# ZX1541_Interfac_in_THT.net
KiCad netlist of a schematic drawn in Altium Designer
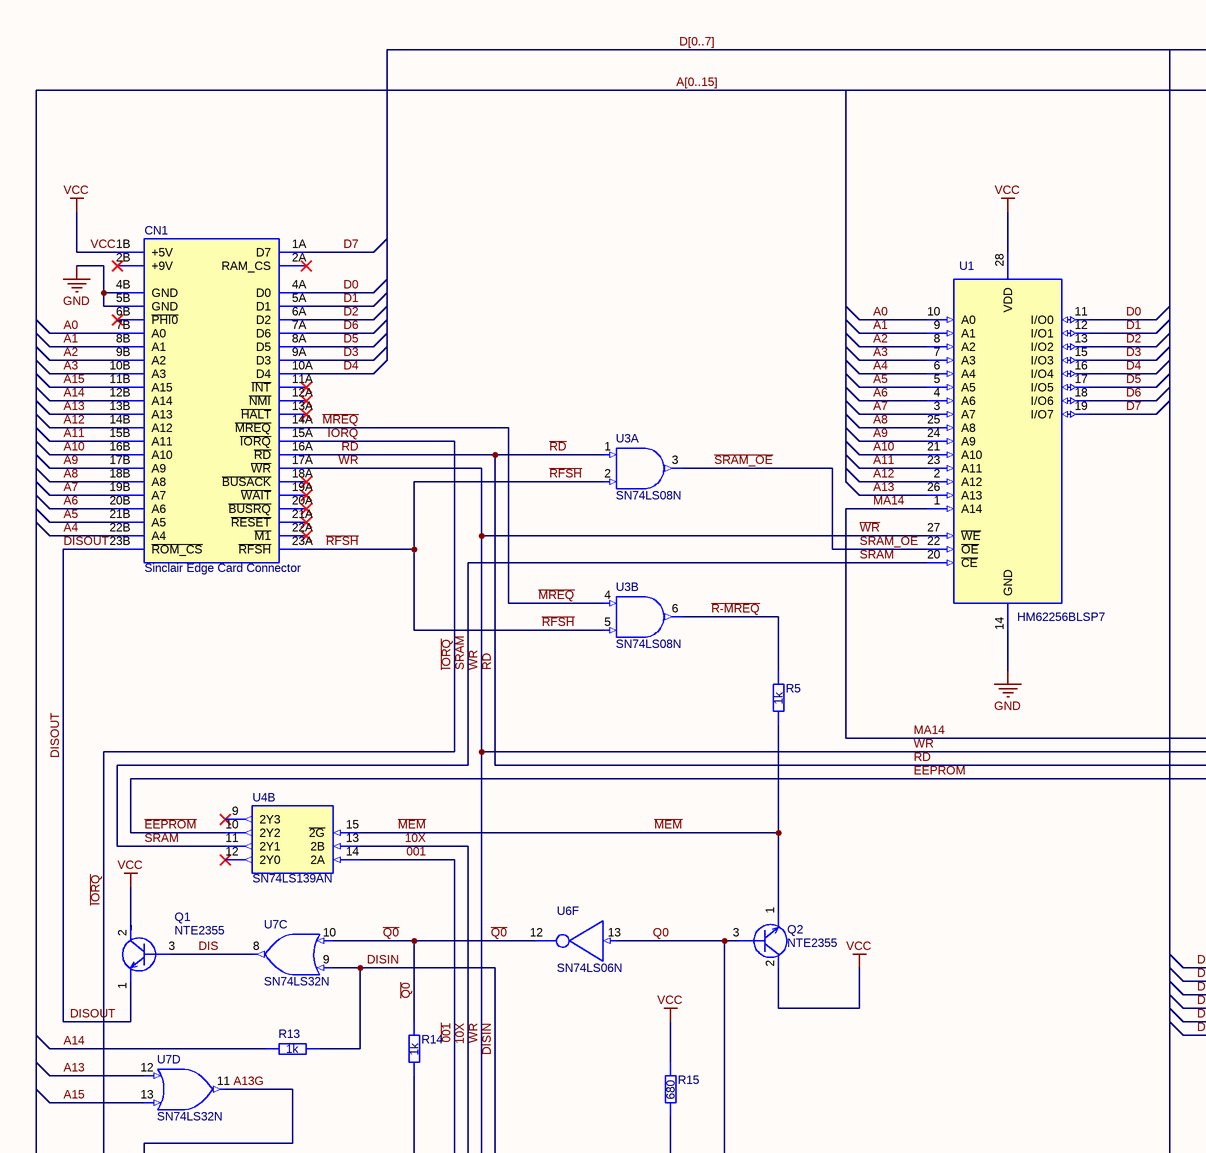
[diagram p0: ZX1541 Interfac in THT.SchDoc, top left]
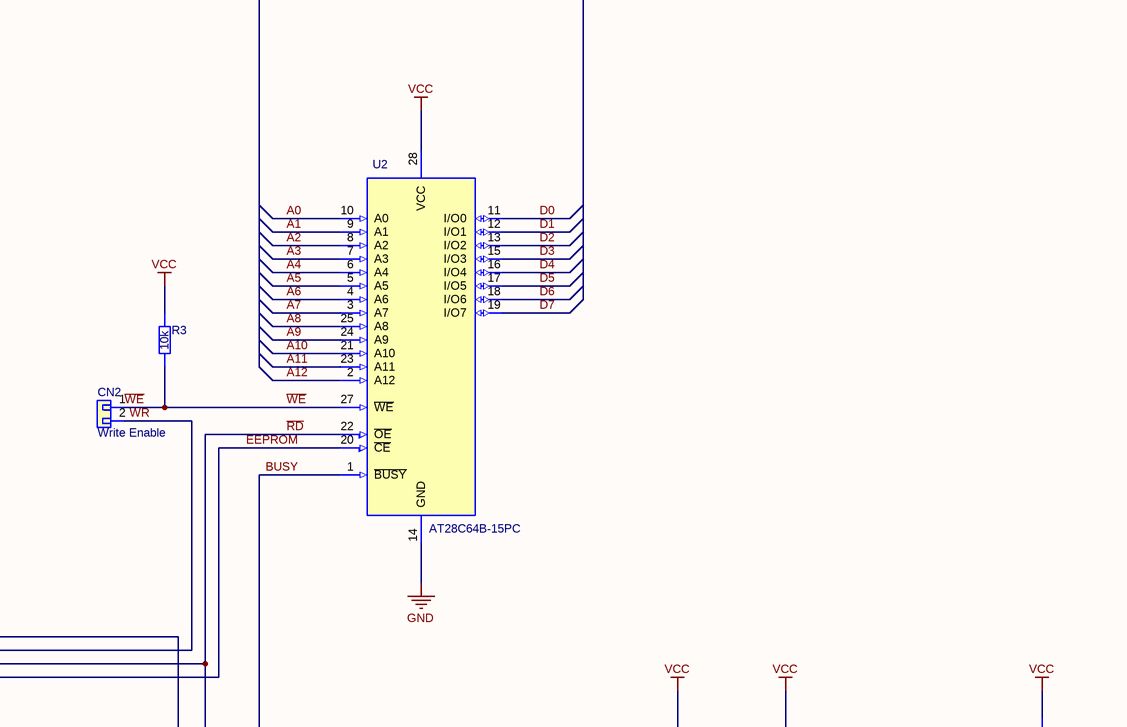
[diagram p1: ZX1541 Interfac in THT.SchDoc, top right]
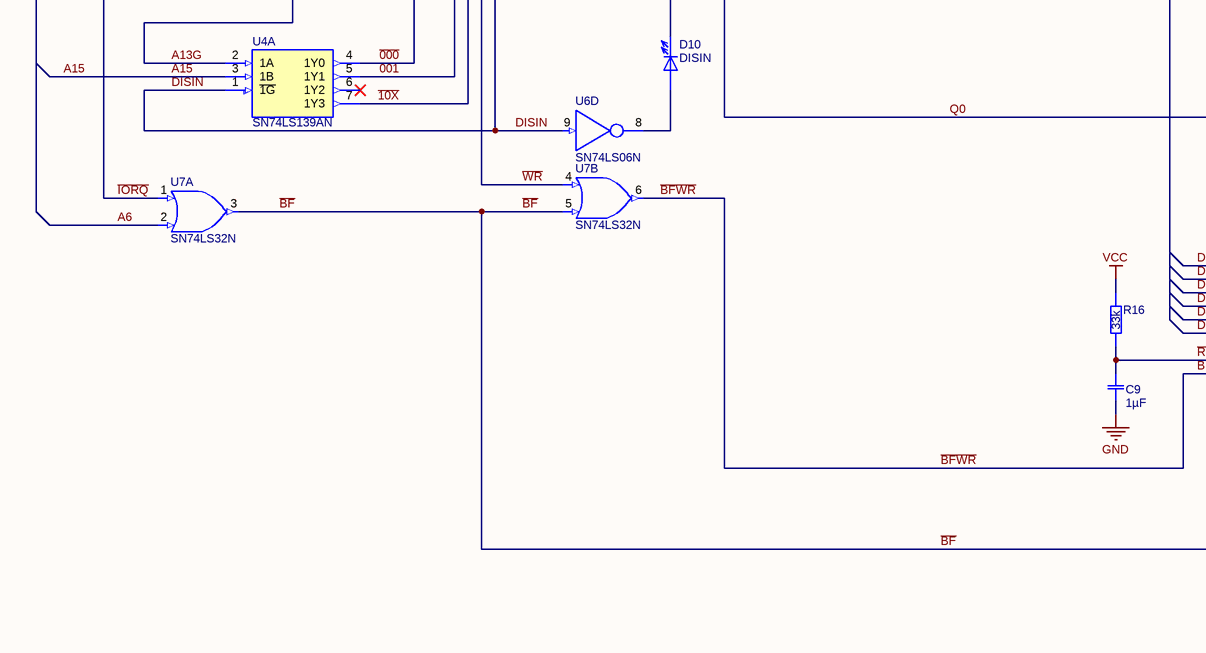
[diagram p2: ZX1541 Interfac in THT.SchDoc, bottom left]
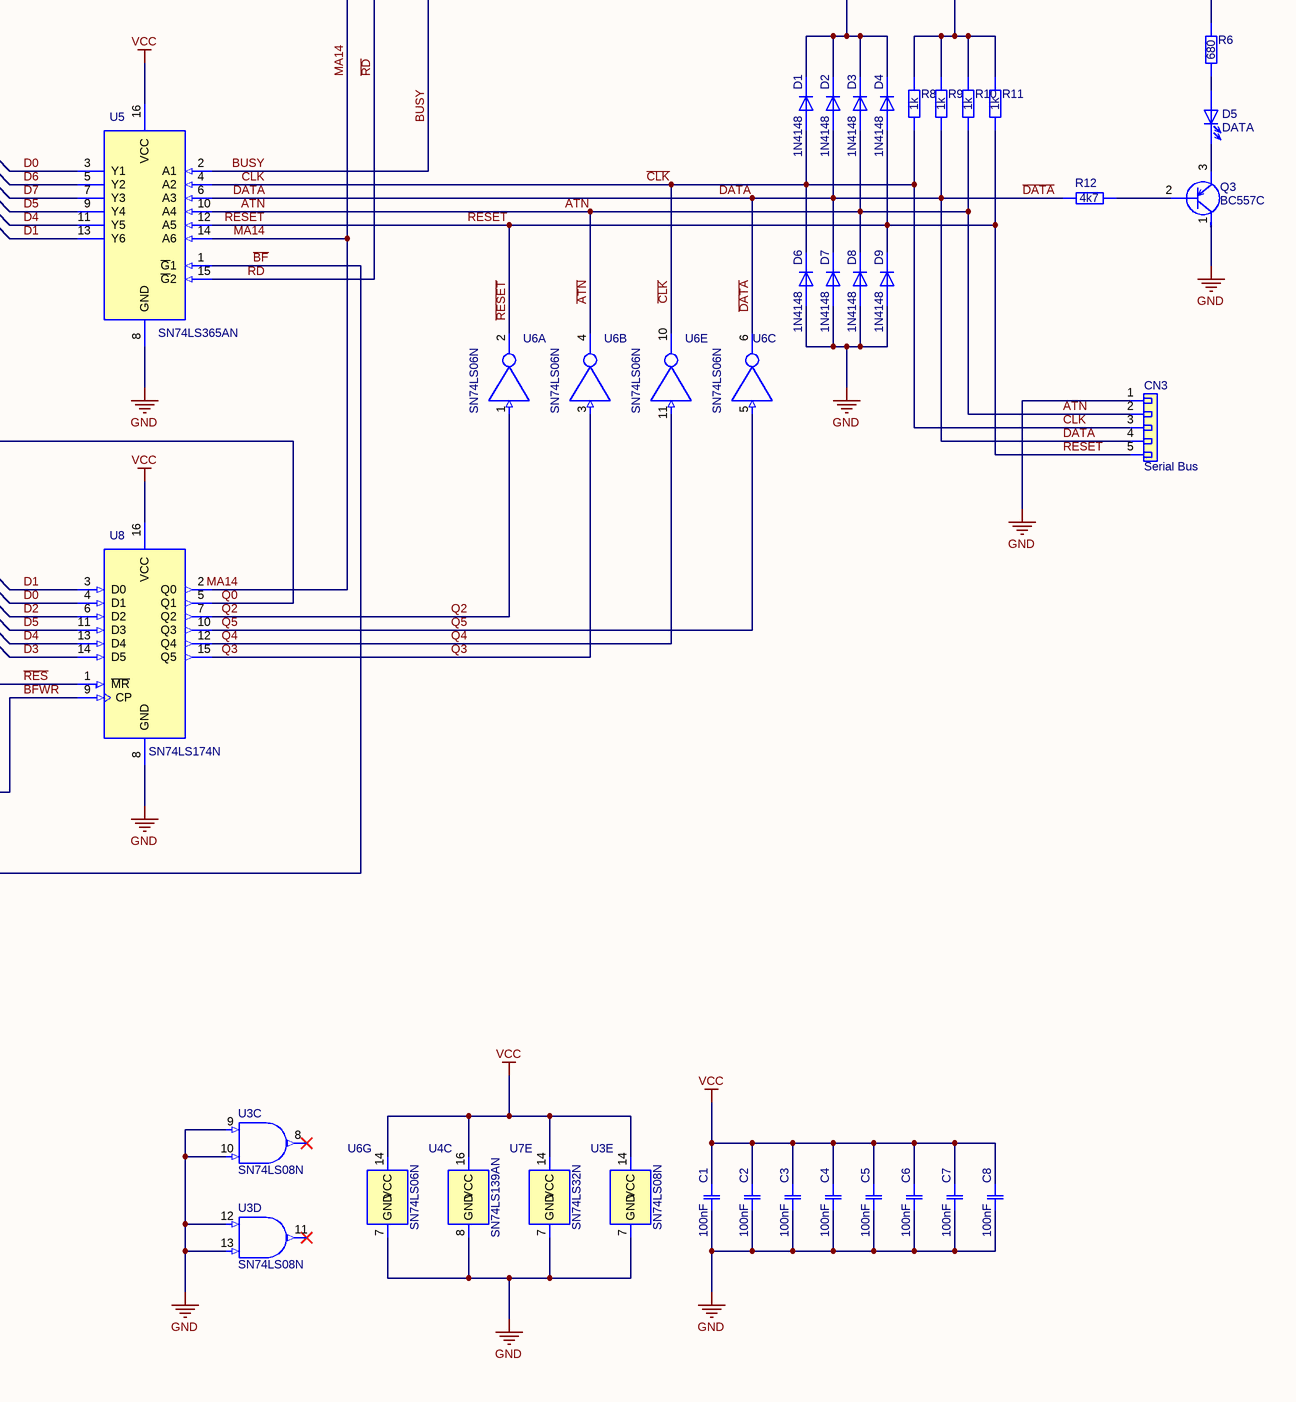
[diagram p3: ZX1541 Interfac in THT.SchDoc, bottom right]

(export (version "E")
  (design (tool "Eeschema 10.0.6"))
  (components
    (comp (ref "C1")
      (value "100nF")
      (footprint "CAP Disc 100nF P2.54mm D5.5mm T3mm")
      (description "Ceramic Disc Capacitors 100nF -20%~+80% 50V Through Hole,P=2.54mm RoHS")
      (libsource (lib "PCB-Tech Cloud") (part "Capacitor"))
    )
    (comp (ref "C2")
      (value "100nF")
      (footprint "CAP Disc 100nF P2.54mm D5.5mm T3mm")
      (description "Ceramic Disc Capacitors 100nF -20%~+80% 50V Through Hole,P=2.54mm RoHS")
      (libsource (lib "PCB-Tech Cloud") (part "Capacitor"))
    )
    (comp (ref "C3")
      (value "100nF")
      (footprint "CAP Disc 100nF P2.54mm D5.5mm T3mm")
      (description "Ceramic Disc Capacitors 100nF -20%~+80% 50V Through Hole,P=2.54mm RoHS")
      (libsource (lib "PCB-Tech Cloud") (part "Capacitor"))
    )
    (comp (ref "C4")
      (value "100nF")
      (footprint "CAP Disc 100nF P2.54mm D5.5mm T3mm")
      (description "Ceramic Disc Capacitors 100nF -20%~+80% 50V Through Hole,P=2.54mm RoHS")
      (libsource (lib "PCB-Tech Cloud") (part "Capacitor"))
    )
    (comp (ref "C5")
      (value "100nF")
      (footprint "CAP Disc 100nF P2.54mm D5.5mm T3mm")
      (description "Ceramic Disc Capacitors 100nF -20%~+80% 50V Through Hole,P=2.54mm RoHS")
      (libsource (lib "PCB-Tech Cloud") (part "Capacitor"))
    )
    (comp (ref "C6")
      (value "100nF")
      (footprint "CAP Disc 100nF P2.54mm D5.5mm T3mm")
      (description "Ceramic Disc Capacitors 100nF -20%~+80% 50V Through Hole,P=2.54mm RoHS")
      (libsource (lib "PCB-Tech Cloud") (part "Capacitor"))
    )
    (comp (ref "C7")
      (value "100nF")
      (footprint "CAP Disc 100nF P2.54mm D5.5mm T3mm")
      (description "Ceramic Disc Capacitors 100nF -20%~+80% 50V Through Hole,P=2.54mm RoHS")
      (libsource (lib "PCB-Tech Cloud") (part "Capacitor"))
    )
    (comp (ref "C8")
      (value "100nF")
      (footprint "CAP Disc 100nF P2.54mm D5.5mm T3mm")
      (description "Ceramic Disc Capacitors 100nF -20%~+80% 50V Through Hole,P=2.54mm RoHS")
      (libsource (lib "PCB-Tech Cloud") (part "Capacitor"))
    )
    (comp (ref "C9")
      (value "1µF")
      (footprint "CAP 1µF C315C105K3R5TA P2.54mm")
      (description "Multilayer Ceramic Capacitors MLCC - Leaded 25volts 1uF 10% X7R")
      (fields (field (name "VOLTAGE") "25V") (field (name "TOLERANCE") "10%"))
      (libsource (lib "PCB-Tech Cloud") (part "Capacitor"))
    )
    (comp (ref "CN1")
      (value "Sinclair Edge Card Connector")
      (footprint "Sinclair Card Connector")
      (libsource (lib "PCB-Tech Cloud") (part "Sinclair Expansion Port Connector"))
    )
    (comp (ref "CN2")
      (value "Write Enable")
      (footprint "Pin Header 01x02 2.54mm Horizontal Male")
      (description "CONN HEADER .100\" SNGL STR 2POS")
      (libsource (lib "PCB-Tech Cloud") (part "CONN 01x02"))
    )
    (comp (ref "CN3")
      (value "Serial Bus")
      (footprint "01x05 RM2.0 mm Male Pin Header - MPE-Garry 150-1-005-0-S-XS0-0835")
      (description "Conn Unshrouded Header HDR 5 POS 2mm Solder ST Thru-Hole Automotive Bulk")
      (libsource (lib "PCB-Tech Cloud") (part "CONN 01x05"))
    )
    (comp (ref "D1")
      (value "1N4148")
      (footprint "1N4148 P=5.08mm")
      (description "NEXPERIA - 1N4148 - DIODE, 1N4148 AMMO-BOX 10K")
      (fields (field (name "VOLTAGE") "100V"))
      (libsource (lib "PCB-Tech Cloud") (part "Diode Standard"))
    )
    (comp (ref "D2")
      (value "1N4148")
      (footprint "1N4148 P=5.08mm")
      (description "NEXPERIA - 1N4148 - DIODE, 1N4148 AMMO-BOX 10K")
      (fields (field (name "VOLTAGE") "100V"))
      (libsource (lib "PCB-Tech Cloud") (part "Diode Standard"))
    )
    (comp (ref "D3")
      (value "1N4148")
      (footprint "1N4148 P=5.08mm")
      (description "NEXPERIA - 1N4148 - DIODE, 1N4148 AMMO-BOX 10K")
      (fields (field (name "VOLTAGE") "100V"))
      (libsource (lib "PCB-Tech Cloud") (part "Diode Standard"))
    )
    (comp (ref "D4")
      (value "1N4148")
      (footprint "1N4148 P=5.08mm")
      (description "NEXPERIA - 1N4148 - DIODE, 1N4148 AMMO-BOX 10K")
      (fields (field (name "VOLTAGE") "100V"))
      (libsource (lib "PCB-Tech Cloud") (part "Diode Standard"))
    )
    (comp (ref "D5")
      (value "DATA")
      (footprint "LED 3mm Red Right Angle 4mm")
      (description "WURTH ELEKTRONIK   151033RS03000   LED, 3MM,  RED, 2600MCD, 621NM")
      (libsource (lib "PCB-Tech Cloud") (part "LED Standard"))
    )
    (comp (ref "D6")
      (value "1N4148")
      (footprint "1N4148 P=5.08mm")
      (description "NEXPERIA - 1N4148 - DIODE, 1N4148 AMMO-BOX 10K")
      (fields (field (name "VOLTAGE") "100V"))
      (libsource (lib "PCB-Tech Cloud") (part "Diode Standard"))
    )
    (comp (ref "D7")
      (value "1N4148")
      (footprint "1N4148 P=5.08mm")
      (description "NEXPERIA - 1N4148 - DIODE, 1N4148 AMMO-BOX 10K")
      (fields (field (name "VOLTAGE") "100V"))
      (libsource (lib "PCB-Tech Cloud") (part "Diode Standard"))
    )
    (comp (ref "D8")
      (value "1N4148")
      (footprint "1N4148 P=5.08mm")
      (description "NEXPERIA - 1N4148 - DIODE, 1N4148 AMMO-BOX 10K")
      (fields (field (name "VOLTAGE") "100V"))
      (libsource (lib "PCB-Tech Cloud") (part "Diode Standard"))
    )
    (comp (ref "D9")
      (value "1N4148")
      (footprint "1N4148 P=5.08mm")
      (description "NEXPERIA - 1N4148 - DIODE, 1N4148 AMMO-BOX 10K")
      (fields (field (name "VOLTAGE") "100V"))
      (libsource (lib "PCB-Tech Cloud") (part "Diode Standard"))
    )
    (comp (ref "D10")
      (value "DISIN")
      (footprint "LED 3mm Green Right Angle 4mm")
      (libsource (lib "PCB-Tech Cloud") (part "LED Standard"))
    )
    (comp (ref "Q1")
      (value "NTE2355")
      (footprint "NTE 2355")
      (libsource (lib "PCB-Tech Cloud") (part "Transistor NPN ECB"))
    )
    (comp (ref "Q2")
      (value "NTE2355")
      (footprint "NTE 2355")
      (libsource (lib "PCB-Tech Cloud") (part "Transistor NPN ECB"))
    )
    (comp (ref "Q3")
      (value "BC557C")
      (footprint "BC557C")
      (description "Trans GP BJT PNP 45V 0.1A Automotive 3-Pin TO-92 T/R")
      (libsource (lib "PCB-Tech Cloud") (part "Transistor PNP CBE"))
    )
    (comp (ref "R3")
      (value "10k")
      (footprint "10 kOhm R Axial DIN0207 L6.3mm D2.5mm P7.62mm Horizontal")
      (description "RES 10K OHM 1/4W 5% AXIAL")
      (fields (field (name "TOLERANCE") "5%"))
      (libsource (lib "PCB-Tech Cloud") (part "Resistor"))
    )
    (comp (ref "R5")
      (value "1k")
      (footprint "1,0 kOhm R Axial DIN0207 L6.3mm D2.5mm P7.62mm Horizontal")
      (description "RES 1K OHM 1/4W 5% AXIAL")
      (fields (field (name "TOLERANCE") "5%"))
      (libsource (lib "PCB-Tech Cloud") (part "Resistor"))
    )
    (comp (ref "R6")
      (value "680")
      (footprint "680 kOhm R Axial DIN0207 L6.3mm D2.5mm P7.62mm Horizontal")
      (description "Res 680K Ohm 1/4W 5% Axial")
      (fields (field (name "TOLERANCE") "5%"))
      (libsource (lib "PCB-Tech Cloud") (part "Resistor"))
    )
    (comp (ref "R8")
      (value "1k")
      (footprint "1,0 kOhm R Axial DIN0207 L6.3mm D2.5mm P7.62mm Horizontal")
      (description "RES 1K OHM 1/4W 5% AXIAL")
      (fields (field (name "TOLERANCE") "5%"))
      (libsource (lib "PCB-Tech Cloud") (part "Resistor"))
    )
    (comp (ref "R9")
      (value "1k")
      (footprint "1,0 kOhm R Axial DIN0207 L6.3mm D2.5mm P7.62mm Horizontal")
      (description "RES 1K OHM 1/4W 5% AXIAL")
      (fields (field (name "TOLERANCE") "5%"))
      (libsource (lib "PCB-Tech Cloud") (part "Resistor"))
    )
    (comp (ref "R10")
      (value "1k")
      (footprint "1,0 kOhm R Axial DIN0207 L6.3mm D2.5mm P7.62mm Horizontal")
      (description "RES 1K OHM 1/4W 5% AXIAL")
      (fields (field (name "TOLERANCE") "5%"))
      (libsource (lib "PCB-Tech Cloud") (part "Resistor"))
    )
    (comp (ref "R11")
      (value "1k")
      (footprint "1,0 kOhm R Axial DIN0207 L6.3mm D2.5mm P7.62mm Horizontal")
      (description "RES 1K OHM 1/4W 5% AXIAL")
      (fields (field (name "TOLERANCE") "5%"))
      (libsource (lib "PCB-Tech Cloud") (part "Resistor"))
    )
    (comp (ref "R12")
      (value "4k7")
      (footprint "4,7 kOhm R Axial DIN0207 L6.3mm D2.5mm P7.62mm Horizontal")
      (description "RES 4.7K OHM 1/4W 5% AXIAL")
      (fields (field (name "TOLERANCE") "5%"))
      (libsource (lib "PCB-Tech Cloud") (part "Resistor"))
    )
    (comp (ref "R13")
      (value "1k")
      (footprint "1,0 kOhm R Axial DIN0207 L6.3mm D2.5mm P7.62mm Horizontal")
      (description "RES 1K OHM 1/4W 5% AXIAL")
      (fields (field (name "TOLERANCE") "5%"))
      (libsource (lib "PCB-Tech Cloud") (part "Resistor"))
    )
    (comp (ref "R14")
      (value "1k")
      (footprint "1,0 kOhm R Axial DIN0207 L6.3mm D2.5mm P7.62mm Horizontal")
      (description "RES 1K OHM 1/4W 5% AXIAL")
      (fields (field (name "TOLERANCE") "5%"))
      (libsource (lib "PCB-Tech Cloud") (part "Resistor"))
    )
    (comp (ref "R15")
      (value "680")
      (footprint "680 kOhm R Axial DIN0207 L6.3mm D2.5mm P7.62mm Horizontal")
      (description "Res 680K Ohm 1/4W 5% Axial")
      (fields (field (name "TOLERANCE") "5%"))
      (libsource (lib "PCB-Tech Cloud") (part "Resistor"))
    )
    (comp (ref "R16")
      (value "33k")
      (footprint "33 kOhm R Axial DIN0207 L6.3mm D2.5mm P7.62mm Horizontal")
      (description "RES 33K OHM 1/4W 5% AXIAL")
      (fields (field (name "TOLERANCE") "5%"))
      (libsource (lib "PCB-Tech Cloud") (part "Resistor"))
    )
    (comp (ref "U1")
      (value "HM62256BLSP7")
      (footprint "Hitachi HM62256BLSP-7 SRAM 32kx8")
      (description "Contact for details")
      (libsource (lib "PCB-Tech Cloud") (part "HM62256BLSP-7"))
    )
    (comp (ref "U2")
      (value "AT28C64B-15PC")
      (footprint "28C64-150 with precision Socket")
      (description "IC EEPROM 64KBIT 150NS 28DIP")
      (libsource (lib "PCB-Tech Cloud") (part "28PIN 8kx8 EEPROM 28C64"))
    )
    (comp (ref "U3")
      (value "SN74LS08N")
      (footprint "SN74LS08N with Socket")
      (description "IC GATE AND 4CH 2-INP 14DIP")
      (libsource (lib "PCB-Tech Cloud") (part "74xx08"))
    )
    (comp (ref "U4")
      (value "SN74LS139AN")
      (footprint "SN74LS139N with Socket")
      (description "TEXAS INSTRUMENTS         SN74LS139AN            IC, DECODER/DEMUX, 74LS139")
      (libsource (lib "") (part "74xx139_1"))
    )
    (comp (ref "U5")
      (value "SN74LS365AN")
      (footprint "SN74LS365A with Socket")
      (description "Buffer/Line Driver 6-CH Non-Inverting 3-ST Bipolar 16-Pin PDIP Tube")
      (libsource (lib "PCB-Tech Cloud") (part "74xx365"))
    )
    (comp (ref "U6")
      (value "SN74LS06N")
      (footprint "SN74LS06N with Socket")
      (description "IC INVERTER OPEN COL 6CH 14DIP")
      (libsource (lib "") (part "74xx06_2"))
    )
    (comp (ref "U7")
      (value "SN74LS32N")
      (footprint "SN74LS32N with Socket")
      (description "Texas Instruments SN74LS32N, Quad 2-Input OR Logic Gate, 4.75  5.25 V, 14-Pin PDIP")
      (libsource (lib "PCB-Tech Cloud") (part "74xx32"))
    )
    (comp (ref "U8")
      (value "SN74LS174N")
      (footprint "SN74LS174N with Socket")
      (description "Flip Flop D-Type Bus Interface Pos-Edge 1-Element 16-Pin PDIP Tube")
      (libsource (lib "PCB-Tech Cloud") (part "74xx174"))
    )
  )
  (nets
    (net (code "1") (name "/A0") (class "Default")
      (node (ref "CN1") (pin "7B") (pinfunction "A0_7B") (pintype "passive"))
      (node (ref "U1") (pin "10") (pinfunction "A0_10") (pintype "input"))
      (node (ref "U2") (pin "10") (pinfunction "A0_10") (pintype "input"))
    )
    (net (code "2") (name "/A1") (class "Default")
      (node (ref "CN1") (pin "8B") (pinfunction "A1_8B") (pintype "passive"))
      (node (ref "U1") (pin "9") (pinfunction "A1_9") (pintype "input"))
      (node (ref "U2") (pin "9") (pinfunction "A1_9") (pintype "input"))
    )
    (net (code "3") (name "/A2") (class "Default")
      (node (ref "CN1") (pin "9B") (pinfunction "A2_9B") (pintype "passive"))
      (node (ref "U1") (pin "8") (pinfunction "A2_8") (pintype "input"))
      (node (ref "U2") (pin "8") (pinfunction "A2_8") (pintype "input"))
    )
    (net (code "4") (name "/A3") (class "Default")
      (node (ref "CN1") (pin "10B") (pinfunction "A3_10B") (pintype "passive"))
      (node (ref "U1") (pin "7") (pinfunction "A3_7") (pintype "input"))
      (node (ref "U2") (pin "7") (pinfunction "A3_7") (pintype "input"))
    )
    (net (code "5") (name "/A4") (class "Default")
      (node (ref "CN1") (pin "22B") (pinfunction "A4_22B") (pintype "passive"))
      (node (ref "U1") (pin "6") (pinfunction "A4_6") (pintype "input"))
      (node (ref "U2") (pin "6") (pinfunction "A4_6") (pintype "input"))
    )
    (net (code "6") (name "/A5") (class "Default")
      (node (ref "CN1") (pin "21B") (pinfunction "A5_21B") (pintype "passive"))
      (node (ref "U1") (pin "5") (pinfunction "A5_5") (pintype "input"))
      (node (ref "U2") (pin "5") (pinfunction "A5_5") (pintype "input"))
    )
    (net (code "7") (name "/A6") (class "Default")
      (node (ref "CN1") (pin "20B") (pinfunction "A6_20B") (pintype "passive"))
      (node (ref "U1") (pin "4") (pinfunction "A6_4") (pintype "input"))
      (node (ref "U2") (pin "4") (pinfunction "A6_4") (pintype "input"))
      (node (ref "U7") (pin "2") (pinfunction "1B_2") (pintype "input"))
    )
    (net (code "8") (name "/A7") (class "Default")
      (node (ref "CN1") (pin "19B") (pinfunction "A7_19B") (pintype "passive"))
      (node (ref "U1") (pin "3") (pinfunction "A7_3") (pintype "input"))
      (node (ref "U2") (pin "3") (pinfunction "A7_3") (pintype "input"))
    )
    (net (code "9") (name "/A8") (class "Default")
      (node (ref "CN1") (pin "18B") (pinfunction "A8_18B") (pintype "passive"))
      (node (ref "U1") (pin "25") (pinfunction "A8_25") (pintype "input"))
      (node (ref "U2") (pin "25") (pinfunction "A8_25") (pintype "input"))
    )
    (net (code "10") (name "/A9") (class "Default")
      (node (ref "CN1") (pin "17B") (pinfunction "A9_17B") (pintype "passive"))
      (node (ref "U1") (pin "24") (pinfunction "A9_24") (pintype "input"))
      (node (ref "U2") (pin "24") (pinfunction "A9_24") (pintype "input"))
    )
    (net (code "11") (name "/A10") (class "Default")
      (node (ref "CN1") (pin "16B") (pinfunction "A10_16B") (pintype "passive"))
      (node (ref "U1") (pin "21") (pinfunction "A10_21") (pintype "input"))
      (node (ref "U2") (pin "21") (pinfunction "A10_21") (pintype "input"))
    )
    (net (code "12") (name "/A11") (class "Default")
      (node (ref "CN1") (pin "15B") (pinfunction "A11_15B") (pintype "passive"))
      (node (ref "U1") (pin "23") (pinfunction "A11_23") (pintype "input"))
      (node (ref "U2") (pin "23") (pinfunction "A11_23") (pintype "input"))
    )
    (net (code "13") (name "/A12") (class "Default")
      (node (ref "CN1") (pin "14B") (pinfunction "A12_14B") (pintype "passive"))
      (node (ref "U1") (pin "2") (pinfunction "A12_2") (pintype "input"))
      (node (ref "U2") (pin "2") (pinfunction "A12_2") (pintype "input"))
    )
    (net (code "14") (name "/A13") (class "Default")
      (node (ref "CN1") (pin "13B") (pinfunction "A13_13B") (pintype "passive"))
      (node (ref "U1") (pin "26") (pinfunction "A13_26") (pintype "input"))
      (node (ref "U7") (pin "12") (pinfunction "4A_12") (pintype "input"))
    )
    (net (code "15") (name "/A13G") (class "Default")
      (node (ref "U4") (pin "2") (pinfunction "1A_2") (pintype "input"))
      (node (ref "U7") (pin "11") (pinfunction "4Y_11") (pintype "output"))
    )
    (net (code "16") (name "/A14") (class "Default")
      (node (ref "CN1") (pin "12B") (pinfunction "A14_12B") (pintype "passive"))
      (node (ref "R13") (pin "1") (pinfunction "1_1") (pintype "passive"))
    )
    (net (code "17") (name "/A15") (class "Default")
      (node (ref "CN1") (pin "11B") (pinfunction "A15_11B") (pintype "passive"))
      (node (ref "U4") (pin "3") (pinfunction "1B_3") (pintype "input"))
      (node (ref "U7") (pin "13") (pinfunction "4B_13") (pintype "input"))
    )
    (net (code "19") (name "/BUSY") (class "Default")
      (node (ref "U2") (pin "1") (pinfunction "~{BUSY}_1") (pintype "input"))
      (node (ref "U5") (pin "2") (pinfunction "A1_2") (pintype "input"))
    )
    (net (code "20") (name "/D0") (class "Default")
      (node (ref "CN1") (pin "4A") (pinfunction "D0_4A") (pintype "passive"))
      (node (ref "U1") (pin "11") (pinfunction "I/O0_11") (pintype "bidirectional"))
      (node (ref "U2") (pin "11") (pinfunction "I/O0_11") (pintype "bidirectional"))
      (node (ref "U5") (pin "3") (pinfunction "Y1_3") (pintype "open_collector"))
      (node (ref "U8") (pin "4") (pinfunction "D1_4") (pintype "input"))
    )
    (net (code "21") (name "/D1") (class "Default")
      (node (ref "CN1") (pin "5A") (pinfunction "D1_5A") (pintype "passive"))
      (node (ref "U1") (pin "12") (pinfunction "I/O1_12") (pintype "bidirectional"))
      (node (ref "U2") (pin "12") (pinfunction "I/O1_12") (pintype "bidirectional"))
      (node (ref "U5") (pin "13") (pinfunction "Y6_13") (pintype "open_collector"))
      (node (ref "U8") (pin "3") (pinfunction "D0_3") (pintype "input"))
    )
    (net (code "22") (name "/D2") (class "Default")
      (node (ref "CN1") (pin "6A") (pinfunction "D2_6A") (pintype "passive"))
      (node (ref "U1") (pin "13") (pinfunction "I/O2_13") (pintype "bidirectional"))
      (node (ref "U2") (pin "13") (pinfunction "I/O2_13") (pintype "bidirectional"))
      (node (ref "U8") (pin "6") (pinfunction "D2_6") (pintype "input"))
    )
    (net (code "23") (name "/D3") (class "Default")
      (node (ref "CN1") (pin "9A") (pinfunction "D3_9A") (pintype "passive"))
      (node (ref "U1") (pin "15") (pinfunction "I/O3_15") (pintype "bidirectional"))
      (node (ref "U2") (pin "15") (pinfunction "I/O3_15") (pintype "bidirectional"))
      (node (ref "U8") (pin "14") (pinfunction "D5_14") (pintype "input"))
    )
    (net (code "24") (name "/D4") (class "Default")
      (node (ref "CN1") (pin "10A") (pinfunction "D4_10A") (pintype "passive"))
      (node (ref "U1") (pin "16") (pinfunction "I/O4_16") (pintype "bidirectional"))
      (node (ref "U2") (pin "16") (pinfunction "I/O4_16") (pintype "bidirectional"))
      (node (ref "U5") (pin "11") (pinfunction "Y5_11") (pintype "open_collector"))
      (node (ref "U8") (pin "13") (pinfunction "D4_13") (pintype "input"))
    )
    (net (code "25") (name "/D5") (class "Default")
      (node (ref "CN1") (pin "8A") (pinfunction "D5_8A") (pintype "passive"))
      (node (ref "U1") (pin "17") (pinfunction "I/O5_17") (pintype "bidirectional"))
      (node (ref "U2") (pin "17") (pinfunction "I/O5_17") (pintype "bidirectional"))
      (node (ref "U5") (pin "9") (pinfunction "Y4_9") (pintype "open_collector"))
      (node (ref "U8") (pin "11") (pinfunction "D3_11") (pintype "input"))
    )
    (net (code "26") (name "/D6") (class "Default")
      (node (ref "CN1") (pin "7A") (pinfunction "D6_7A") (pintype "passive"))
      (node (ref "U1") (pin "18") (pinfunction "I/O6_18") (pintype "bidirectional"))
      (node (ref "U2") (pin "18") (pinfunction "I/O6_18") (pintype "bidirectional"))
      (node (ref "U5") (pin "5") (pinfunction "Y2_5") (pintype "open_collector"))
    )
    (net (code "27") (name "/D7") (class "Default")
      (node (ref "CN1") (pin "1A") (pinfunction "D7_1A") (pintype "passive"))
      (node (ref "U1") (pin "19") (pinfunction "I/O7_19") (pintype "bidirectional"))
      (node (ref "U2") (pin "19") (pinfunction "I/O7_19") (pintype "bidirectional"))
      (node (ref "U5") (pin "7") (pinfunction "Y3_7") (pintype "open_collector"))
    )
    (net (code "28") (name "/DIS") (class "Default")
      (node (ref "Q1") (pin "3") (pinfunction "3_3") (pintype "passive"))
      (node (ref "U7") (pin "8") (pinfunction "3Y_8") (pintype "output"))
    )
    (net (code "29") (name "/DISIN") (class "Default")
      (node (ref "R13") (pin "2") (pinfunction "2_2") (pintype "passive"))
      (node (ref "U4") (pin "1") (pinfunction "~{1G}_1") (pintype "input"))
      (node (ref "U6") (pin "9") (pinfunction "4A_9") (pintype "input"))
      (node (ref "U7") (pin "9") (pinfunction "3A_9") (pintype "input"))
    )
    (net (code "30") (name "/DISOUT") (class "Default")
      (node (ref "CN1") (pin "23B") (pinfunction "~{ROM_CS}_23B") (pintype "passive"))
      (node (ref "Q1") (pin "1") (pinfunction "1_1") (pintype "passive"))
    )
    (net (code "32") (name "/MA14") (class "Default")
      (node (ref "U1") (pin "1") (pinfunction "A14_1") (pintype "input"))
      (node (ref "U5") (pin "14") (pinfunction "A6_14") (pintype "input"))
      (node (ref "U8") (pin "2") (pinfunction "Q0_2") (pintype "output"))
    )
    (net (code "33") (name "/Q0") (class "Default")
      (node (ref "Q2") (pin "3") (pinfunction "3_3") (pintype "passive"))
      (node (ref "U6") (pin "13") (pinfunction "6A_13") (pintype "input"))
      (node (ref "U8") (pin "5") (pinfunction "Q1_5") (pintype "output"))
    )
    (net (code "34") (name "/Q2") (class "Default")
      (node (ref "U6") (pin "1") (pinfunction "1A_1") (pintype "input"))
      (node (ref "U8") (pin "7") (pinfunction "Q2_7") (pintype "output"))
    )
    (net (code "35") (name "/Q3") (class "Default")
      (node (ref "U6") (pin "3") (pinfunction "2A_3") (pintype "input"))
      (node (ref "U8") (pin "15") (pinfunction "Q5_15") (pintype "output"))
    )
    (net (code "36") (name "/Q4") (class "Default")
      (node (ref "U6") (pin "11") (pinfunction "5A_11") (pintype "input"))
      (node (ref "U8") (pin "12") (pinfunction "Q4_12") (pintype "output"))
    )
    (net (code "37") (name "/Q5") (class "Default")
      (node (ref "U6") (pin "5") (pinfunction "3A_5") (pintype "input"))
      (node (ref "U8") (pin "10") (pinfunction "Q3_10") (pintype "output"))
    )
    (net (code "38") (name "/~{000}") (class "Default")
      (node (ref "R14") (pin "1") (pinfunction "1_1") (pintype "passive"))
      (node (ref "U4") (pin "4") (pinfunction "1Y0_4") (pintype "output"))
    )
    (net (code "39") (name "/~{001}") (class "Default")
      (node (ref "U4") (pin "14") (pinfunction "2A_14") (pintype "input"))
      (node (ref "U4") (pin "5") (pinfunction "1Y1_5") (pintype "output"))
    )
    (net (code "40") (name "/~{10X}") (class "Default")
      (node (ref "U4") (pin "13") (pinfunction "2B_13") (pintype "input"))
      (node (ref "U4") (pin "7") (pinfunction "1Y3_7") (pintype "output"))
    )
    (net (code "41") (name "/~{ATN}") (class "Default")
      (node (ref "CN3") (pin "2") (pinfunction "2_2") (pintype "passive"))
      (node (ref "D3") (pin "2") (pinfunction "2_2") (pintype "passive"))
      (node (ref "D8") (pin "1") (pinfunction "1_1") (pintype "passive"))
      (node (ref "R10") (pin "1") (pinfunction "1_1") (pintype "passive"))
      (node (ref "U5") (pin "10") (pinfunction "A4_10") (pintype "input"))
      (node (ref "U6") (pin "4") (pinfunction "2Y_4") (pintype "open_collector"))
    )
    (net (code "42") (name "/~{BFWR}") (class "Default")
      (node (ref "U7") (pin "6") (pinfunction "2Y_6") (pintype "output"))
      (node (ref "U8") (pin "9") (pinfunction "CP_9") (pintype "input"))
    )
    (net (code "43") (name "/~{BF}") (class "Default")
      (node (ref "U5") (pin "1") (pinfunction "~{G}1_1") (pintype "input"))
      (node (ref "U7") (pin "3") (pinfunction "1Y_3") (pintype "output"))
      (node (ref "U7") (pin "5") (pinfunction "2B_5") (pintype "input"))
    )
    (net (code "44") (name "/~{CLK}") (class "Default")
      (node (ref "CN3") (pin "3") (pinfunction "3_3") (pintype "passive"))
      (node (ref "D1") (pin "2") (pinfunction "2_2") (pintype "passive"))
      (node (ref "D6") (pin "1") (pinfunction "1_1") (pintype "passive"))
      (node (ref "R8") (pin "1") (pinfunction "1_1") (pintype "passive"))
      (node (ref "U5") (pin "4") (pinfunction "A2_4") (pintype "input"))
      (node (ref "U6") (pin "10") (pinfunction "5Y_10") (pintype "open_collector"))
    )
    (net (code "45") (name "/~{DATA}") (class "Default")
      (node (ref "CN3") (pin "4") (pinfunction "4_4") (pintype "passive"))
      (node (ref "D2") (pin "2") (pinfunction "2_2") (pintype "passive"))
      (node (ref "D7") (pin "1") (pinfunction "1_1") (pintype "passive"))
      (node (ref "R12") (pin "1") (pinfunction "1_1") (pintype "passive"))
      (node (ref "R9") (pin "1") (pinfunction "1_1") (pintype "passive"))
      (node (ref "U5") (pin "6") (pinfunction "A3_6") (pintype "input"))
      (node (ref "U6") (pin "6") (pinfunction "3Y_6") (pintype "open_collector"))
    )
    (net (code "46") (name "/~{EEPROM}") (class "Default")
      (node (ref "U2") (pin "20") (pinfunction "~{CE}_20") (pintype "input"))
      (node (ref "U4") (pin "10") (pinfunction "2Y2_10") (pintype "output"))
    )
    (net (code "47") (name "/~{IORQ}") (class "Default")
      (node (ref "CN1") (pin "15A") (pinfunction "~{IORQ}_15A") (pintype "passive"))
      (node (ref "U7") (pin "1") (pinfunction "1A_1") (pintype "input"))
    )
    (net (code "48") (name "/~{MEM}") (class "Default")
      (node (ref "Q2") (pin "1") (pinfunction "1_1") (pintype "passive"))
      (node (ref "R5") (pin "1") (pinfunction "1_1") (pintype "passive"))
      (node (ref "U4") (pin "15") (pinfunction "~{2G}_15") (pintype "input"))
    )
    (net (code "49") (name "/~{MREQ}") (class "Default")
      (node (ref "CN1") (pin "14A") (pinfunction "~{MREQ}_14A") (pintype "passive"))
      (node (ref "U3") (pin "4") (pinfunction "2A_4") (pintype "input"))
    )
    (net (code "50") (name "/~{Q0}") (class "Default")
      (node (ref "R14") (pin "2") (pinfunction "2_2") (pintype "passive"))
      (node (ref "U6") (pin "12") (pinfunction "6Y_12") (pintype "open_collector"))
      (node (ref "U7") (pin "10") (pinfunction "3B_10") (pintype "input"))
    )
    (net (code "51") (name "/~{R-MREQ}") (class "Default")
      (node (ref "R5") (pin "2") (pinfunction "2_2") (pintype "passive"))
      (node (ref "U3") (pin "6") (pinfunction "2Y_6") (pintype "output"))
    )
    (net (code "52") (name "/~{RD}") (class "Default")
      (node (ref "CN1") (pin "16A") (pinfunction "~{RD}_16A") (pintype "passive"))
      (node (ref "U2") (pin "22") (pinfunction "~{OE}_22") (pintype "input"))
      (node (ref "U3") (pin "1") (pinfunction "1A_1") (pintype "input"))
      (node (ref "U5") (pin "15") (pinfunction "~{G}2_15") (pintype "input"))
    )
    (net (code "53") (name "/~{RESET}") (class "Default")
      (node (ref "CN3") (pin "5") (pinfunction "5_5") (pintype "passive"))
      (node (ref "D4") (pin "2") (pinfunction "2_2") (pintype "passive"))
      (node (ref "D9") (pin "1") (pinfunction "1_1") (pintype "passive"))
      (node (ref "R11") (pin "1") (pinfunction "1_1") (pintype "passive"))
      (node (ref "U5") (pin "12") (pinfunction "A5_12") (pintype "input"))
      (node (ref "U6") (pin "2") (pinfunction "1Y_2") (pintype "open_collector"))
    )
    (net (code "54") (name "/~{RES}") (class "Default")
      (node (ref "C9") (pin "2") (pinfunction "2_2") (pintype "passive"))
      (node (ref "R16") (pin "1") (pinfunction "1_1") (pintype "passive"))
      (node (ref "U8") (pin "1") (pinfunction "~{MR}_1") (pintype "input"))
    )
    (net (code "55") (name "/~{RFSH}") (class "Default")
      (node (ref "CN1") (pin "23A") (pinfunction "~{RFSH}_23A") (pintype "passive"))
      (node (ref "U3") (pin "2") (pinfunction "1B_2") (pintype "input"))
      (node (ref "U3") (pin "5") (pinfunction "2B_5") (pintype "input"))
    )
    (net (code "56") (name "/~{SRAM_OE}") (class "Default")
      (node (ref "U1") (pin "22") (pinfunction "~{OE}_22") (pintype "input"))
      (node (ref "U3") (pin "3") (pinfunction "1Y_3") (pintype "output"))
    )
    (net (code "57") (name "/~{SRAM}") (class "Default")
      (node (ref "U1") (pin "20") (pinfunction "~{CE}_20") (pintype "input"))
      (node (ref "U4") (pin "11") (pinfunction "2Y1_11") (pintype "output"))
    )
    (net (code "58") (name "/~{WE}") (class "Default")
      (node (ref "CN2") (pin "1") (pinfunction "1_1") (pintype "passive"))
      (node (ref "R3") (pin "1") (pinfunction "1_1") (pintype "passive"))
      (node (ref "U2") (pin "27") (pinfunction "~{WE}_27") (pintype "input"))
    )
    (net (code "59") (name "/~{WR}") (class "Default")
      (node (ref "CN1") (pin "17A") (pinfunction "~{WR}_17A") (pintype "passive"))
      (node (ref "CN2") (pin "2") (pinfunction "2_2") (pintype "passive"))
      (node (ref "U1") (pin "27") (pinfunction "~{WE}_27") (pintype "input"))
      (node (ref "U7") (pin "4") (pinfunction "2A_4") (pintype "input"))
    )
    (net (code "60") (name "GND") (class "Default")
      (node (ref "C1") (pin "1") (pinfunction "1_1") (pintype "passive"))
      (node (ref "C2") (pin "1") (pinfunction "1_1") (pintype "passive"))
      (node (ref "C3") (pin "1") (pinfunction "1_1") (pintype "passive"))
      (node (ref "C4") (pin "1") (pinfunction "1_1") (pintype "passive"))
      (node (ref "C5") (pin "1") (pinfunction "1_1") (pintype "passive"))
      (node (ref "C6") (pin "1") (pinfunction "1_1") (pintype "passive"))
      (node (ref "C7") (pin "1") (pinfunction "1_1") (pintype "passive"))
      (node (ref "C8") (pin "1") (pinfunction "1_1") (pintype "passive"))
      (node (ref "C9") (pin "1") (pinfunction "1_1") (pintype "passive"))
      (node (ref "CN1") (pin "4B") (pinfunction "GND_4B") (pintype "power_in"))
      (node (ref "CN1") (pin "5B") (pinfunction "GND_5B") (pintype "power_in"))
      (node (ref "CN3") (pin "1") (pinfunction "1_1") (pintype "passive"))
      (node (ref "D6") (pin "2") (pinfunction "2_2") (pintype "passive"))
      (node (ref "D7") (pin "2") (pinfunction "2_2") (pintype "passive"))
      (node (ref "D8") (pin "2") (pinfunction "2_2") (pintype "passive"))
      (node (ref "D9") (pin "2") (pinfunction "2_2") (pintype "passive"))
      (node (ref "Q3") (pin "1") (pinfunction "1_1") (pintype "passive"))
      (node (ref "U1") (pin "14") (pinfunction "GND_14") (pintype "power_in"))
      (node (ref "U2") (pin "14") (pinfunction "GND_14") (pintype "power_in"))
      (node (ref "U3") (pin "10") (pinfunction "3B_10") (pintype "input"))
      (node (ref "U3") (pin "12") (pinfunction "4A_12") (pintype "input"))
      (node (ref "U3") (pin "13") (pinfunction "4B_13") (pintype "input"))
      (node (ref "U3") (pin "7") (pinfunction "GND_7") (pintype "passive"))
      (node (ref "U3") (pin "9") (pinfunction "3A_9") (pintype "input"))
      (node (ref "U4") (pin "8") (pinfunction "GND_8") (pintype "passive"))
      (node (ref "U5") (pin "8") (pinfunction "GND_8") (pintype "power_in"))
      (node (ref "U6") (pin "7") (pinfunction "GND_7") (pintype "passive"))
      (node (ref "U7") (pin "7") (pinfunction "GND_7") (pintype "passive"))
      (node (ref "U8") (pin "8") (pinfunction "GND_8") (pintype "power_in"))
    )
    (net (code "61") (name "Net-(D5-Pad1)") (class "Default")
      (node (ref "D5") (pin "1") (pinfunction "1_1") (pintype "passive"))
      (node (ref "Q3") (pin "3") (pinfunction "3_3") (pintype "passive"))
    )
    (net (code "62") (name "Net-(D5-Pad2)") (class "Default")
      (node (ref "D5") (pin "2") (pinfunction "2_2") (pintype "passive"))
      (node (ref "R6") (pin "1") (pinfunction "1_1") (pintype "passive"))
    )
    (net (code "63") (name "Net-(D10-Pad1)") (class "Default")
      (node (ref "D10") (pin "1") (pinfunction "1_1") (pintype "passive"))
      (node (ref "R15") (pin "1") (pinfunction "1_1") (pintype "passive"))
    )
    (net (code "64") (name "Net-(Q3-Pad2)") (class "Default")
      (node (ref "Q3") (pin "2") (pinfunction "2_2") (pintype "passive"))
      (node (ref "R12") (pin "2") (pinfunction "2_2") (pintype "passive"))
    )
    (net (code "65") (name "Net-(U6D-4Y)") (class "Default")
      (node (ref "D10") (pin "2") (pinfunction "2_2") (pintype "passive"))
      (node (ref "U6") (pin "8") (pinfunction "4Y_8") (pintype "open_collector"))
    )
    (net (code "66") (name "VCC") (class "Default")
      (node (ref "C1") (pin "2") (pinfunction "2_2") (pintype "passive"))
      (node (ref "C2") (pin "2") (pinfunction "2_2") (pintype "passive"))
      (node (ref "C3") (pin "2") (pinfunction "2_2") (pintype "passive"))
      (node (ref "C4") (pin "2") (pinfunction "2_2") (pintype "passive"))
      (node (ref "C5") (pin "2") (pinfunction "2_2") (pintype "passive"))
      (node (ref "C6") (pin "2") (pinfunction "2_2") (pintype "passive"))
      (node (ref "C7") (pin "2") (pinfunction "2_2") (pintype "passive"))
      (node (ref "C8") (pin "2") (pinfunction "2_2") (pintype "passive"))
      (node (ref "CN1") (pin "1B") (pinfunction "+5V_1B") (pintype "power_in"))
      (node (ref "D1") (pin "1") (pinfunction "1_1") (pintype "passive"))
      (node (ref "D2") (pin "1") (pinfunction "1_1") (pintype "passive"))
      (node (ref "D3") (pin "1") (pinfunction "1_1") (pintype "passive"))
      (node (ref "D4") (pin "1") (pinfunction "1_1") (pintype "passive"))
      (node (ref "Q1") (pin "2") (pinfunction "2_2") (pintype "passive"))
      (node (ref "Q2") (pin "2") (pinfunction "2_2") (pintype "passive"))
      (node (ref "R10") (pin "2") (pinfunction "2_2") (pintype "passive"))
      (node (ref "R11") (pin "2") (pinfunction "2_2") (pintype "passive"))
      (node (ref "R15") (pin "2") (pinfunction "2_2") (pintype "passive"))
      (node (ref "R16") (pin "2") (pinfunction "2_2") (pintype "passive"))
      (node (ref "R3") (pin "2") (pinfunction "2_2") (pintype "passive"))
      (node (ref "R6") (pin "2") (pinfunction "2_2") (pintype "passive"))
      (node (ref "R8") (pin "2") (pinfunction "2_2") (pintype "passive"))
      (node (ref "R9") (pin "2") (pinfunction "2_2") (pintype "passive"))
      (node (ref "U1") (pin "28") (pinfunction "VDD_28") (pintype "power_in"))
      (node (ref "U2") (pin "28") (pinfunction "VCC_28") (pintype "power_in"))
      (node (ref "U3") (pin "14") (pinfunction "VCC_14") (pintype "power_in"))
      (node (ref "U4") (pin "16") (pinfunction "VCC_16") (pintype "power_in"))
      (node (ref "U5") (pin "16") (pinfunction "VCC_16") (pintype "power_in"))
      (node (ref "U6") (pin "14") (pinfunction "VCC_14") (pintype "power_in"))
      (node (ref "U7") (pin "14") (pinfunction "VCC_14") (pintype "power_in"))
      (node (ref "U8") (pin "16") (pinfunction "VCC_16") (pintype "power_in"))
    )
    (net (code "67") (name "unconnected-(CN1-+9V-Pad2B)") (class "Default")
      (node (ref "CN1") (pin "2B") (pinfunction "+9V_2B") (pintype "power_in+no_connect"))
    )
    (net (code "68") (name "unconnected-(CN1-RAM_CS-Pad2A)") (class "Default")
      (node (ref "CN1") (pin "2A") (pinfunction "RAM_CS_2A") (pintype "passive+no_connect"))
    )
    (net (code "69") (name "unconnected-(CN1-~{BUSACK}-Pad18A)") (class "Default")
      (node (ref "CN1") (pin "18A") (pinfunction "~{BUSACK}_18A") (pintype "passive+no_connect"))
    )
    (net (code "70") (name "unconnected-(CN1-~{BUSRQ}-Pad20A)") (class "Default")
      (node (ref "CN1") (pin "20A") (pinfunction "~{BUSRQ}_20A") (pintype "passive+no_connect"))
    )
    (net (code "71") (name "unconnected-(CN1-~{HALT}-Pad13A)") (class "Default")
      (node (ref "CN1") (pin "13A") (pinfunction "~{HALT}_13A") (pintype "passive+no_connect"))
    )
    (net (code "72") (name "unconnected-(CN1-~{INT}-Pad11A)") (class "Default")
      (node (ref "CN1") (pin "11A") (pinfunction "~{INT}_11A") (pintype "passive+no_connect"))
    )
    (net (code "73") (name "unconnected-(CN1-~{M1}-Pad22A)") (class "Default")
      (node (ref "CN1") (pin "22A") (pinfunction "~{M1}_22A") (pintype "passive+no_connect"))
    )
    (net (code "74") (name "unconnected-(CN1-~{NMI}-Pad12A)") (class "Default")
      (node (ref "CN1") (pin "12A") (pinfunction "~{NMI}_12A") (pintype "passive+no_connect"))
    )
    (net (code "75") (name "unconnected-(CN1-~{PHI0}-Pad6B)") (class "Default")
      (node (ref "CN1") (pin "6B") (pinfunction "~{PHI0}_6B") (pintype "passive+no_connect"))
    )
    (net (code "76") (name "unconnected-(CN1-~{RESET}-Pad21A)") (class "Default")
      (node (ref "CN1") (pin "21A") (pinfunction "~{RESET}_21A") (pintype "passive+no_connect"))
    )
    (net (code "77") (name "unconnected-(CN1-~{WAIT}-Pad19A)") (class "Default")
      (node (ref "CN1") (pin "19A") (pinfunction "~{WAIT}_19A") (pintype "passive+no_connect"))
    )
    (net (code "78") (name "unconnected-(U2-N{slash}C-Pad26)") (class "Default")
      (node (ref "U2") (pin "26") (pinfunction "N/C_26") (pintype "passive"))
    )
    (net (code "79") (name "unconnected-(U3C-3Y-Pad8)") (class "Default")
      (node (ref "U3") (pin "8") (pinfunction "3Y_8") (pintype "output+no_connect"))
    )
    (net (code "80") (name "unconnected-(U3D-4Y-Pad11)") (class "Default")
      (node (ref "U3") (pin "11") (pinfunction "4Y_11") (pintype "output+no_connect"))
    )
    (net (code "81") (name "unconnected-(U4A-1Y2-Pad6)") (class "Default")
      (node (ref "U4") (pin "6") (pinfunction "1Y2_6") (pintype "output+no_connect"))
    )
    (net (code "82") (name "unconnected-(U4B-2Y0-Pad12)") (class "Default")
      (node (ref "U4") (pin "12") (pinfunction "2Y0_12") (pintype "output+no_connect"))
    )
    (net (code "83") (name "unconnected-(U4B-2Y3-Pad9)") (class "Default")
      (node (ref "U4") (pin "9") (pinfunction "2Y3_9") (pintype "output+no_connect"))
    )
  )
)
